# CompleteBoard.net
KiCad netlist of a schematic drawn in EAGLE
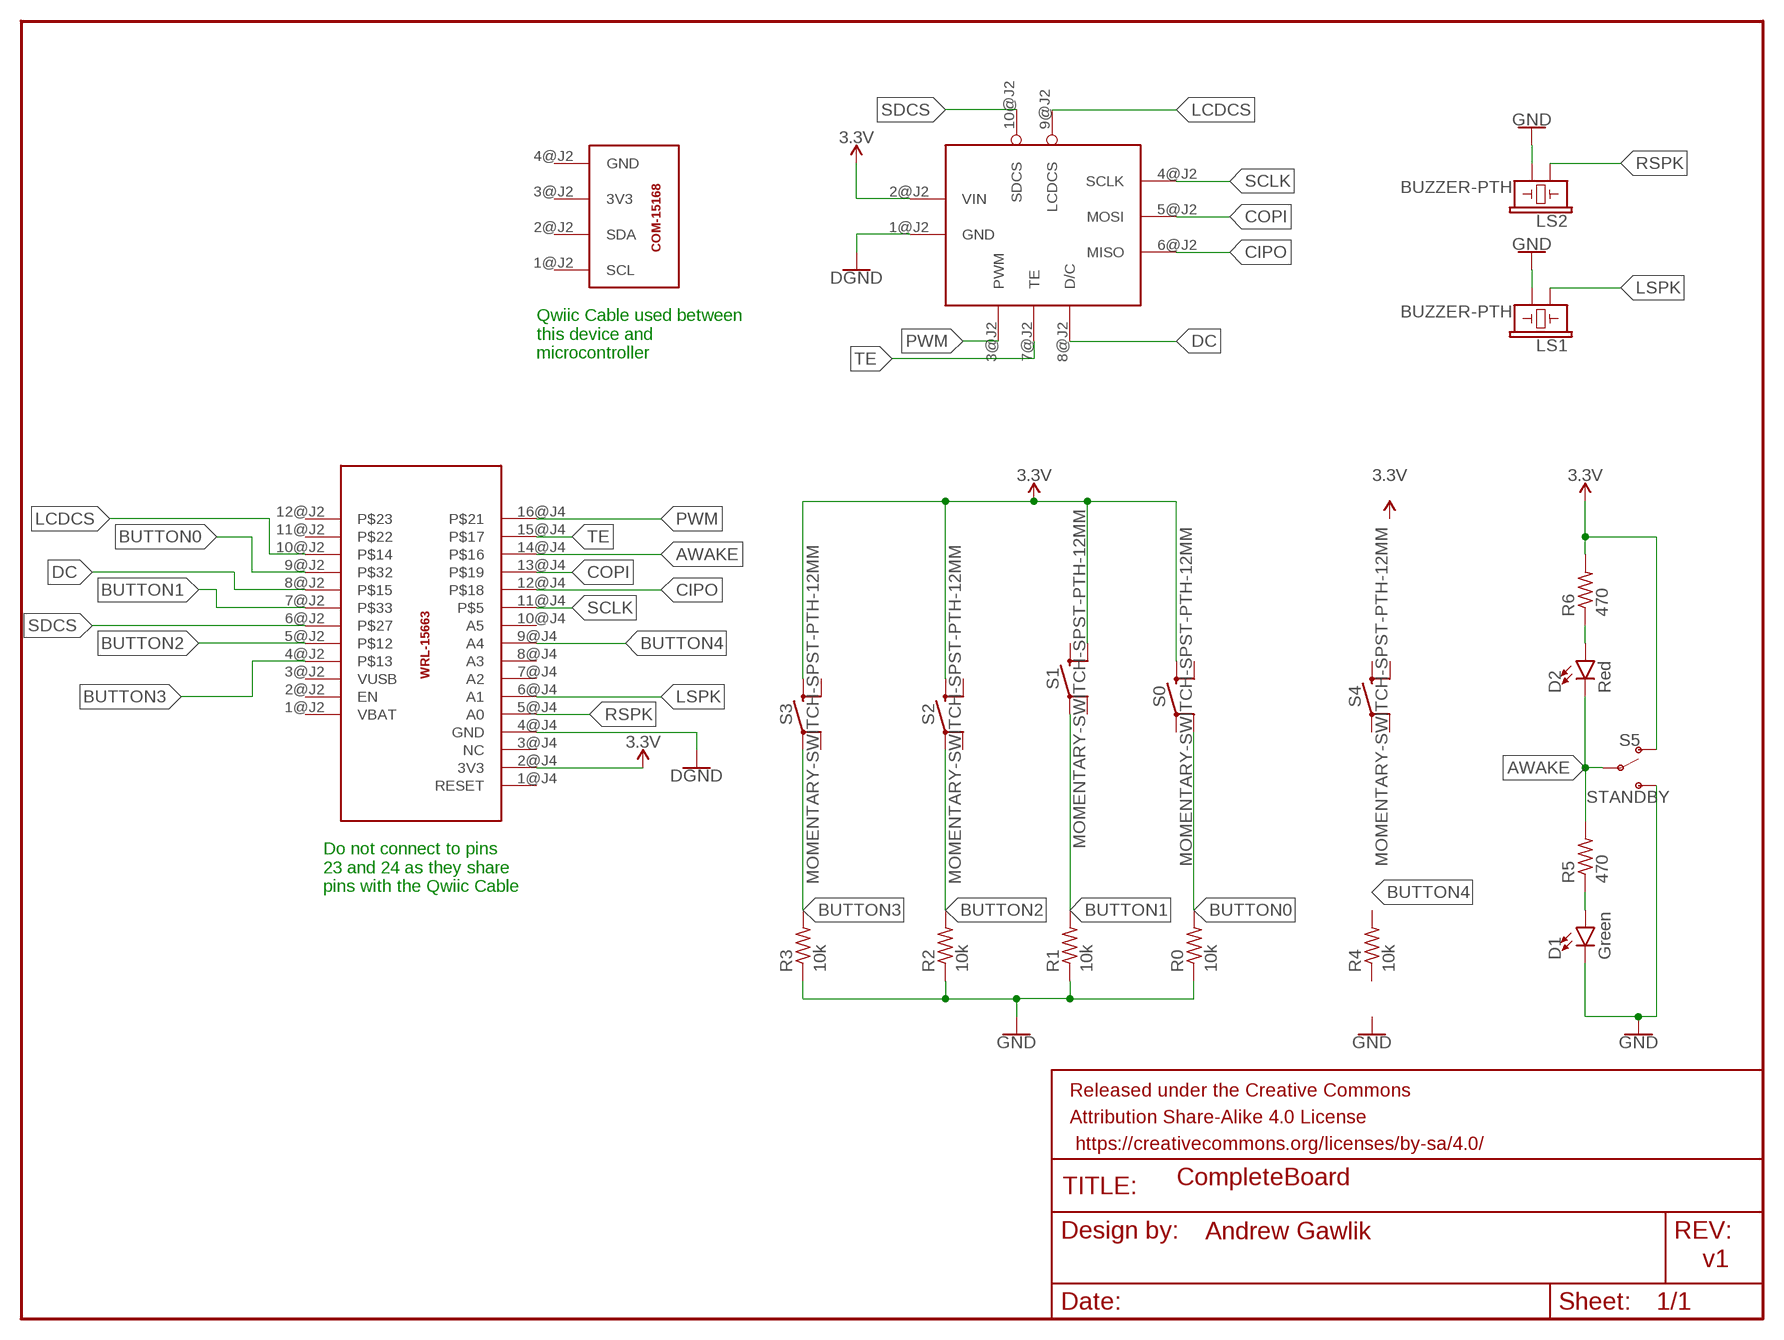
[diagram p0: schematic, sheet 1]

(export (version "E")
  (design (tool "Eeschema 10.0.6"))
  (components
    (comp (ref "A1")
      (value "ESP32_MICROCONTROLLER")
      (footprint "eagle-import:WRL-17381")
      (libsource (lib "eagle-import") (part "WRL-17381"))
    )
    (comp (ref "A2")
      (value "TFT")
      (footprint "eagle-import:LCD-15143")
      (libsource (lib "eagle-import") (part "LCD-15143"))
    )
    (comp (ref "A3")
      (value "COM-15168")
      (footprint "eagle-import:COM-15168")
      (libsource (lib "eagle-import") (part "COM-15168"))
    )
    (comp (ref "D1")
      (value "Green")
      (footprint "eagle-import:LED_5MM-KIT")
      (libsource (lib "eagle-import") (part "LED5MM-KIT"))
    )
    (comp (ref "D2")
      (value "Red")
      (footprint "eagle-import:LED_5MM-KIT")
      (libsource (lib "eagle-import") (part "LED5MM-KIT"))
    )
    (comp (ref "FRAME1")
      (value "001")
      (footprint "eagle-import:CREATIVE_COMMONS")
      (libsource (lib "eagle-import") (part "FRAME-LETTER"))
    )
    (comp (ref "LS1")
      (value "BUZZER-PTH")
      (footprint "eagle-import:BUZZER-12MM")
      (libsource (lib "eagle-import") (part "BUZZER-PTH"))
    )
    (comp (ref "LS2")
      (value "BUZZER-PTH")
      (footprint "eagle-import:BUZZER-12MM")
      (libsource (lib "eagle-import") (part "BUZZER-PTH"))
    )
    (comp (ref "R0")
      (value "10k")
      (footprint "eagle-import:0204_5")
      (libsource (lib "eagle-import") (part "R-US_0204/5"))
    )
    (comp (ref "R1")
      (value "10k")
      (footprint "eagle-import:0204_5")
      (libsource (lib "eagle-import") (part "R-US_0204/5"))
    )
    (comp (ref "R2")
      (value "10k")
      (footprint "eagle-import:0204_5")
      (libsource (lib "eagle-import") (part "R-US_0204/5"))
    )
    (comp (ref "R3")
      (value "10k")
      (footprint "eagle-import:0204_5")
      (libsource (lib "eagle-import") (part "R-US_0204/5"))
    )
    (comp (ref "R4")
      (value "10k")
      (footprint "eagle-import:0204_5")
      (libsource (lib "eagle-import") (part "R-US_0204/5"))
    )
    (comp (ref "R5")
      (value "470")
      (footprint "eagle-import:0204_5")
      (libsource (lib "eagle-import") (part "R-US_0204/5"))
    )
    (comp (ref "R6")
      (value "470")
      (footprint "eagle-import:0204_5")
      (libsource (lib "eagle-import") (part "R-US_0204/5"))
    )
    (comp (ref "S0")
      (value "MOMENTARY-SWITCH-SPST-PTH-12MM")
      (footprint "eagle-import:TACTILE_SWITCH_PTH_12MM")
      (libsource (lib "eagle-import") (part "MOMENTARY-SWITCH-SPST-PTH-12MM"))
    )
    (comp (ref "S1")
      (value "MOMENTARY-SWITCH-SPST-PTH-12MM")
      (footprint "eagle-import:TACTILE_SWITCH_PTH_12MM")
      (libsource (lib "eagle-import") (part "MOMENTARY-SWITCH-SPST-PTH-12MM"))
    )
    (comp (ref "S2")
      (value "MOMENTARY-SWITCH-SPST-PTH-12MM")
      (footprint "eagle-import:TACTILE_SWITCH_PTH_12MM")
      (libsource (lib "eagle-import") (part "MOMENTARY-SWITCH-SPST-PTH-12MM"))
    )
    (comp (ref "S3")
      (value "MOMENTARY-SWITCH-SPST-PTH-12MM")
      (footprint "eagle-import:TACTILE_SWITCH_PTH_12MM")
      (libsource (lib "eagle-import") (part "MOMENTARY-SWITCH-SPST-PTH-12MM"))
    )
    (comp (ref "S4")
      (value "MOMENTARY-SWITCH-SPST-PTH-12MM")
      (footprint "eagle-import:TACTILE_SWITCH_PTH_12MM")
      (libsource (lib "eagle-import") (part "MOMENTARY-SWITCH-SPST-PTH-12MM"))
    )
    (comp (ref "S5")
      (value "STANDBY")
      (footprint "eagle-import:SWITCH_SPDT_PTH_11.6X4.0MM")
      (libsource (lib "eagle-import") (part "SWITCH-SPDT-PTH-11.6X4.0MM"))
    )
  )
  (nets
    (net (code "1") (name "3.3V") (class "Default")
      (node (ref "A1") (pin "2@J4") (pinfunction "3V3_2@J4") (pintype "power_in"))
      (node (ref "A2") (pin "2@J2") (pinfunction "VIN_2@J2") (pintype "power_in"))
      (node (ref "R6") (pin "2") (pinfunction "2_2") (pintype "passive"))
      (node (ref "S0") (pin "3") (pinfunction "3_3") (pintype "passive"))
      (node (ref "S1") (pin "4") (pinfunction "4_4") (pintype "passive"))
      (node (ref "S2") (pin "3") (pinfunction "3_3") (pintype "passive"))
      (node (ref "S3") (pin "3") (pinfunction "3_3") (pintype "passive"))
      (node (ref "S5") (pin "1") (pinfunction "O_1") (pintype "passive"))
    )
    (net (code "2") (name "AWAKE") (class "Default")
      (node (ref "A1") (pin "14@J4") (pinfunction "P$16_14@J4") (pintype "bidirectional"))
      (node (ref "D2") (pin "K") (pinfunction "C_K") (pintype "passive"))
      (node (ref "R5") (pin "2") (pinfunction "2_2") (pintype "passive"))
      (node (ref "S5") (pin "2") (pinfunction "P_2") (pintype "passive"))
    )
    (net (code "3") (name "BUTTON0") (class "Default")
      (node (ref "A1") (pin "9@J2") (pinfunction "P$32_9@J2") (pintype "bidirectional"))
      (node (ref "R0") (pin "2") (pinfunction "2_2") (pintype "passive"))
      (node (ref "S0") (pin "2") (pinfunction "2_2") (pintype "passive"))
    )
    (net (code "4") (name "BUTTON1") (class "Default")
      (node (ref "A1") (pin "7@J2") (pinfunction "P$33_7@J2") (pintype "bidirectional"))
      (node (ref "R1") (pin "2") (pinfunction "2_2") (pintype "passive"))
      (node (ref "S1") (pin "1") (pinfunction "1_1") (pintype "passive"))
    )
    (net (code "5") (name "BUTTON2") (class "Default")
      (node (ref "A1") (pin "5@J2") (pinfunction "P$12_5@J2") (pintype "bidirectional"))
      (node (ref "R2") (pin "2") (pinfunction "2_2") (pintype "passive"))
      (node (ref "S2") (pin "1") (pinfunction "1_1") (pintype "passive"))
    )
    (net (code "6") (name "BUTTON3") (class "Default")
      (node (ref "A1") (pin "4@J2") (pinfunction "P$13_4@J2") (pintype "bidirectional"))
      (node (ref "R3") (pin "2") (pinfunction "2_2") (pintype "passive"))
      (node (ref "S3") (pin "1") (pinfunction "1_1") (pintype "passive"))
    )
    (net (code "7") (name "BUTTON4") (class "Default")
      (node (ref "A1") (pin "9@J4") (pinfunction "A4_9@J4") (pintype "bidirectional"))
    )
    (net (code "8") (name "CIPO") (class "Default")
      (node (ref "A1") (pin "12@J4") (pinfunction "P$18_12@J4") (pintype "bidirectional"))
      (node (ref "A2") (pin "6@J2") (pinfunction "MISO_6@J2") (pintype "output"))
    )
    (net (code "9") (name "COPI") (class "Default")
      (node (ref "A1") (pin "13@J4") (pinfunction "P$19_13@J4") (pintype "bidirectional"))
      (node (ref "A2") (pin "5@J2") (pinfunction "MOSI_5@J2") (pintype "input"))
    )
    (net (code "10") (name "DC") (class "Default")
      (node (ref "A1") (pin "8@J2") (pinfunction "P$15_8@J2") (pintype "bidirectional"))
      (node (ref "A2") (pin "8@J2") (pinfunction "D/C_8@J2") (pintype "bidirectional"))
    )
    (net (code "11") (name "DGND") (class "Default")
      (node (ref "A1") (pin "4@J4") (pinfunction "GND_4@J4") (pintype "power_in"))
      (node (ref "A2") (pin "1@J2") (pinfunction "GND_1@J2") (pintype "power_in"))
      (node (ref "D1") (pin "K") (pinfunction "C_K") (pintype "passive"))
      (node (ref "LS1") (pin "-") (pinfunction "2_-") (pintype "passive"))
      (node (ref "LS2") (pin "-") (pinfunction "2_-") (pintype "passive"))
      (node (ref "R0") (pin "1") (pinfunction "1_1") (pintype "passive"))
      (node (ref "R1") (pin "1") (pinfunction "1_1") (pintype "passive"))
      (node (ref "R2") (pin "1") (pinfunction "1_1") (pintype "passive"))
      (node (ref "R3") (pin "1") (pinfunction "1_1") (pintype "passive"))
      (node (ref "S5") (pin "3") (pinfunction "S_3") (pintype "passive"))
    )
    (net (code "12") (name "LCDCS") (class "Default")
      (node (ref "A1") (pin "10@J2") (pinfunction "P$14_10@J2") (pintype "bidirectional"))
      (node (ref "A2") (pin "9@J2") (pinfunction "LCDCS_9@J2") (pintype "input"))
    )
    (net (code "13") (name "LSPK") (class "Default")
      (node (ref "A1") (pin "6@J4") (pinfunction "A1_6@J4") (pintype "bidirectional"))
      (node (ref "LS1") (pin "+") (pinfunction "1_+") (pintype "passive"))
    )
    (net (code "14") (name "Net-(D1-PadA)") (class "Default")
      (node (ref "D1") (pin "A") (pinfunction "A_A") (pintype "passive"))
      (node (ref "R5") (pin "1") (pinfunction "1_1") (pintype "passive"))
    )
    (net (code "15") (name "Net-(D2-PadA)") (class "Default")
      (node (ref "D2") (pin "A") (pinfunction "A_A") (pintype "passive"))
      (node (ref "R6") (pin "1") (pinfunction "1_1") (pintype "passive"))
    )
    (net (code "16") (name "PWM") (class "Default")
      (node (ref "A1") (pin "16@J4") (pinfunction "P$21_16@J4") (pintype "bidirectional"))
      (node (ref "A2") (pin "3@J2") (pinfunction "PWM_3@J2") (pintype "input"))
    )
    (net (code "17") (name "RSPK") (class "Default")
      (node (ref "A1") (pin "5@J4") (pinfunction "A0_5@J4") (pintype "bidirectional"))
      (node (ref "LS2") (pin "+") (pinfunction "1_+") (pintype "passive"))
    )
    (net (code "18") (name "SCLK") (class "Default")
      (node (ref "A1") (pin "11@J4") (pinfunction "P$5_11@J4") (pintype "bidirectional"))
      (node (ref "A2") (pin "4@J2") (pinfunction "SCLK_4@J2") (pintype "input"))
    )
    (net (code "19") (name "SDCS") (class "Default")
      (node (ref "A1") (pin "6@J2") (pinfunction "P$27_6@J2") (pintype "bidirectional"))
      (node (ref "A2") (pin "10@J2") (pinfunction "SDCS_10@J2") (pintype "input"))
    )
    (net (code "20") (name "TE") (class "Default")
      (node (ref "A1") (pin "15@J4") (pinfunction "P$17_15@J4") (pintype "bidirectional"))
      (node (ref "A2") (pin "7@J2") (pinfunction "TE_7@J2") (pintype "output"))
    )
    (net (code "21") (name "unconnected-(A1-A2-Pad7@J4)") (class "Default")
      (node (ref "A1") (pin "7@J4") (pinfunction "A2_7@J4") (pintype "bidirectional"))
    )
    (net (code "22") (name "unconnected-(A1-A3-Pad8@J4)") (class "Default")
      (node (ref "A1") (pin "8@J4") (pinfunction "A3_8@J4") (pintype "bidirectional"))
    )
    (net (code "23") (name "unconnected-(A1-A5-Pad10@J4)") (class "Default")
      (node (ref "A1") (pin "10@J4") (pinfunction "A5_10@J4") (pintype "bidirectional"))
    )
    (net (code "24") (name "unconnected-(A1-EN-Pad2@J2)") (class "Default")
      (node (ref "A1") (pin "2@J2") (pinfunction "EN_2@J2") (pintype "output"))
    )
    (net (code "25") (name "unconnected-(A1-NC-Pad3@J4)") (class "Default")
      (node (ref "A1") (pin "3@J4") (pinfunction "NC_3@J4") (pintype "no_connect"))
    )
    (net (code "26") (name "unconnected-(A1-P$22-Pad11@J2)") (class "Default")
      (node (ref "A1") (pin "11@J2") (pinfunction "P$22_11@J2") (pintype "bidirectional"))
    )
    (net (code "27") (name "unconnected-(A1-P$23-Pad12@J2)") (class "Default")
      (node (ref "A1") (pin "12@J2") (pinfunction "P$23_12@J2") (pintype "bidirectional"))
    )
    (net (code "28") (name "unconnected-(A1-RESET-Pad1@J4)") (class "Default")
      (node (ref "A1") (pin "1@J4") (pinfunction "RESET_1@J4") (pintype "bidirectional"))
    )
    (net (code "29") (name "unconnected-(A1-VBAT-Pad1@J2)") (class "Default")
      (node (ref "A1") (pin "1@J2") (pinfunction "VBAT_1@J2") (pintype "no_connect"))
    )
    (net (code "30") (name "unconnected-(A1-VUSB-Pad3@J2)") (class "Default")
      (node (ref "A1") (pin "3@J2") (pinfunction "VUSB_3@J2") (pintype "no_connect"))
    )
    (net (code "31") (name "unconnected-(A3-3V3-Pad3@J2)") (class "Default")
      (node (ref "A3") (pin "3@J2") (pinfunction "3V3_3@J2") (pintype "no_connect"))
    )
    (net (code "32") (name "unconnected-(A3-GND-Pad4@J2)") (class "Default")
      (node (ref "A3") (pin "4@J2") (pinfunction "GND_4@J2") (pintype "no_connect"))
    )
    (net (code "33") (name "unconnected-(A3-SCL-Pad1@J2)") (class "Default")
      (node (ref "A3") (pin "1@J2") (pinfunction "SCL_1@J2") (pintype "no_connect"))
    )
    (net (code "34") (name "unconnected-(A3-SDA-Pad2@J2)") (class "Default")
      (node (ref "A3") (pin "2@J2") (pinfunction "SDA_2@J2") (pintype "no_connect"))
    )
    (net (code "35") (name "unconnected-(R4-Pad1)") (class "Default")
      (node (ref "R4") (pin "1") (pinfunction "1_1") (pintype "passive"))
    )
    (net (code "36") (name "unconnected-(R4-Pad2)") (class "Default")
      (node (ref "R4") (pin "2") (pinfunction "2_2") (pintype "passive"))
    )
    (net (code "37") (name "unconnected-(S0-Pad1)") (class "Default")
      (node (ref "S0") (pin "1") (pinfunction "1_1") (pintype "passive"))
    )
    (net (code "38") (name "unconnected-(S0-Pad4)") (class "Default")
      (node (ref "S0") (pin "4") (pinfunction "4_4") (pintype "passive"))
    )
    (net (code "39") (name "unconnected-(S1-Pad2)") (class "Default")
      (node (ref "S1") (pin "2") (pinfunction "2_2") (pintype "passive"))
    )
    (net (code "40") (name "unconnected-(S1-Pad3)") (class "Default")
      (node (ref "S1") (pin "3") (pinfunction "3_3") (pintype "passive"))
    )
    (net (code "41") (name "unconnected-(S2-Pad2)") (class "Default")
      (node (ref "S2") (pin "2") (pinfunction "2_2") (pintype "passive"))
    )
    (net (code "42") (name "unconnected-(S2-Pad4)") (class "Default")
      (node (ref "S2") (pin "4") (pinfunction "4_4") (pintype "passive"))
    )
    (net (code "43") (name "unconnected-(S3-Pad2)") (class "Default")
      (node (ref "S3") (pin "2") (pinfunction "2_2") (pintype "passive"))
    )
    (net (code "44") (name "unconnected-(S3-Pad4)") (class "Default")
      (node (ref "S3") (pin "4") (pinfunction "4_4") (pintype "passive"))
    )
    (net (code "45") (name "unconnected-(S4-Pad1)") (class "Default")
      (node (ref "S4") (pin "1") (pinfunction "1_1") (pintype "passive"))
    )
    (net (code "46") (name "unconnected-(S4-Pad2)") (class "Default")
      (node (ref "S4") (pin "2") (pinfunction "2_2") (pintype "passive"))
    )
    (net (code "47") (name "unconnected-(S4-Pad3)") (class "Default")
      (node (ref "S4") (pin "3") (pinfunction "3_3") (pintype "passive"))
    )
    (net (code "48") (name "unconnected-(S4-Pad4)") (class "Default")
      (node (ref "S4") (pin "4") (pinfunction "4_4") (pintype "passive"))
    )
  )
)
